# SensorNodePCB_set1_v2_wo_Relay.net
KiCad netlist of a schematic drawn in EAGLE
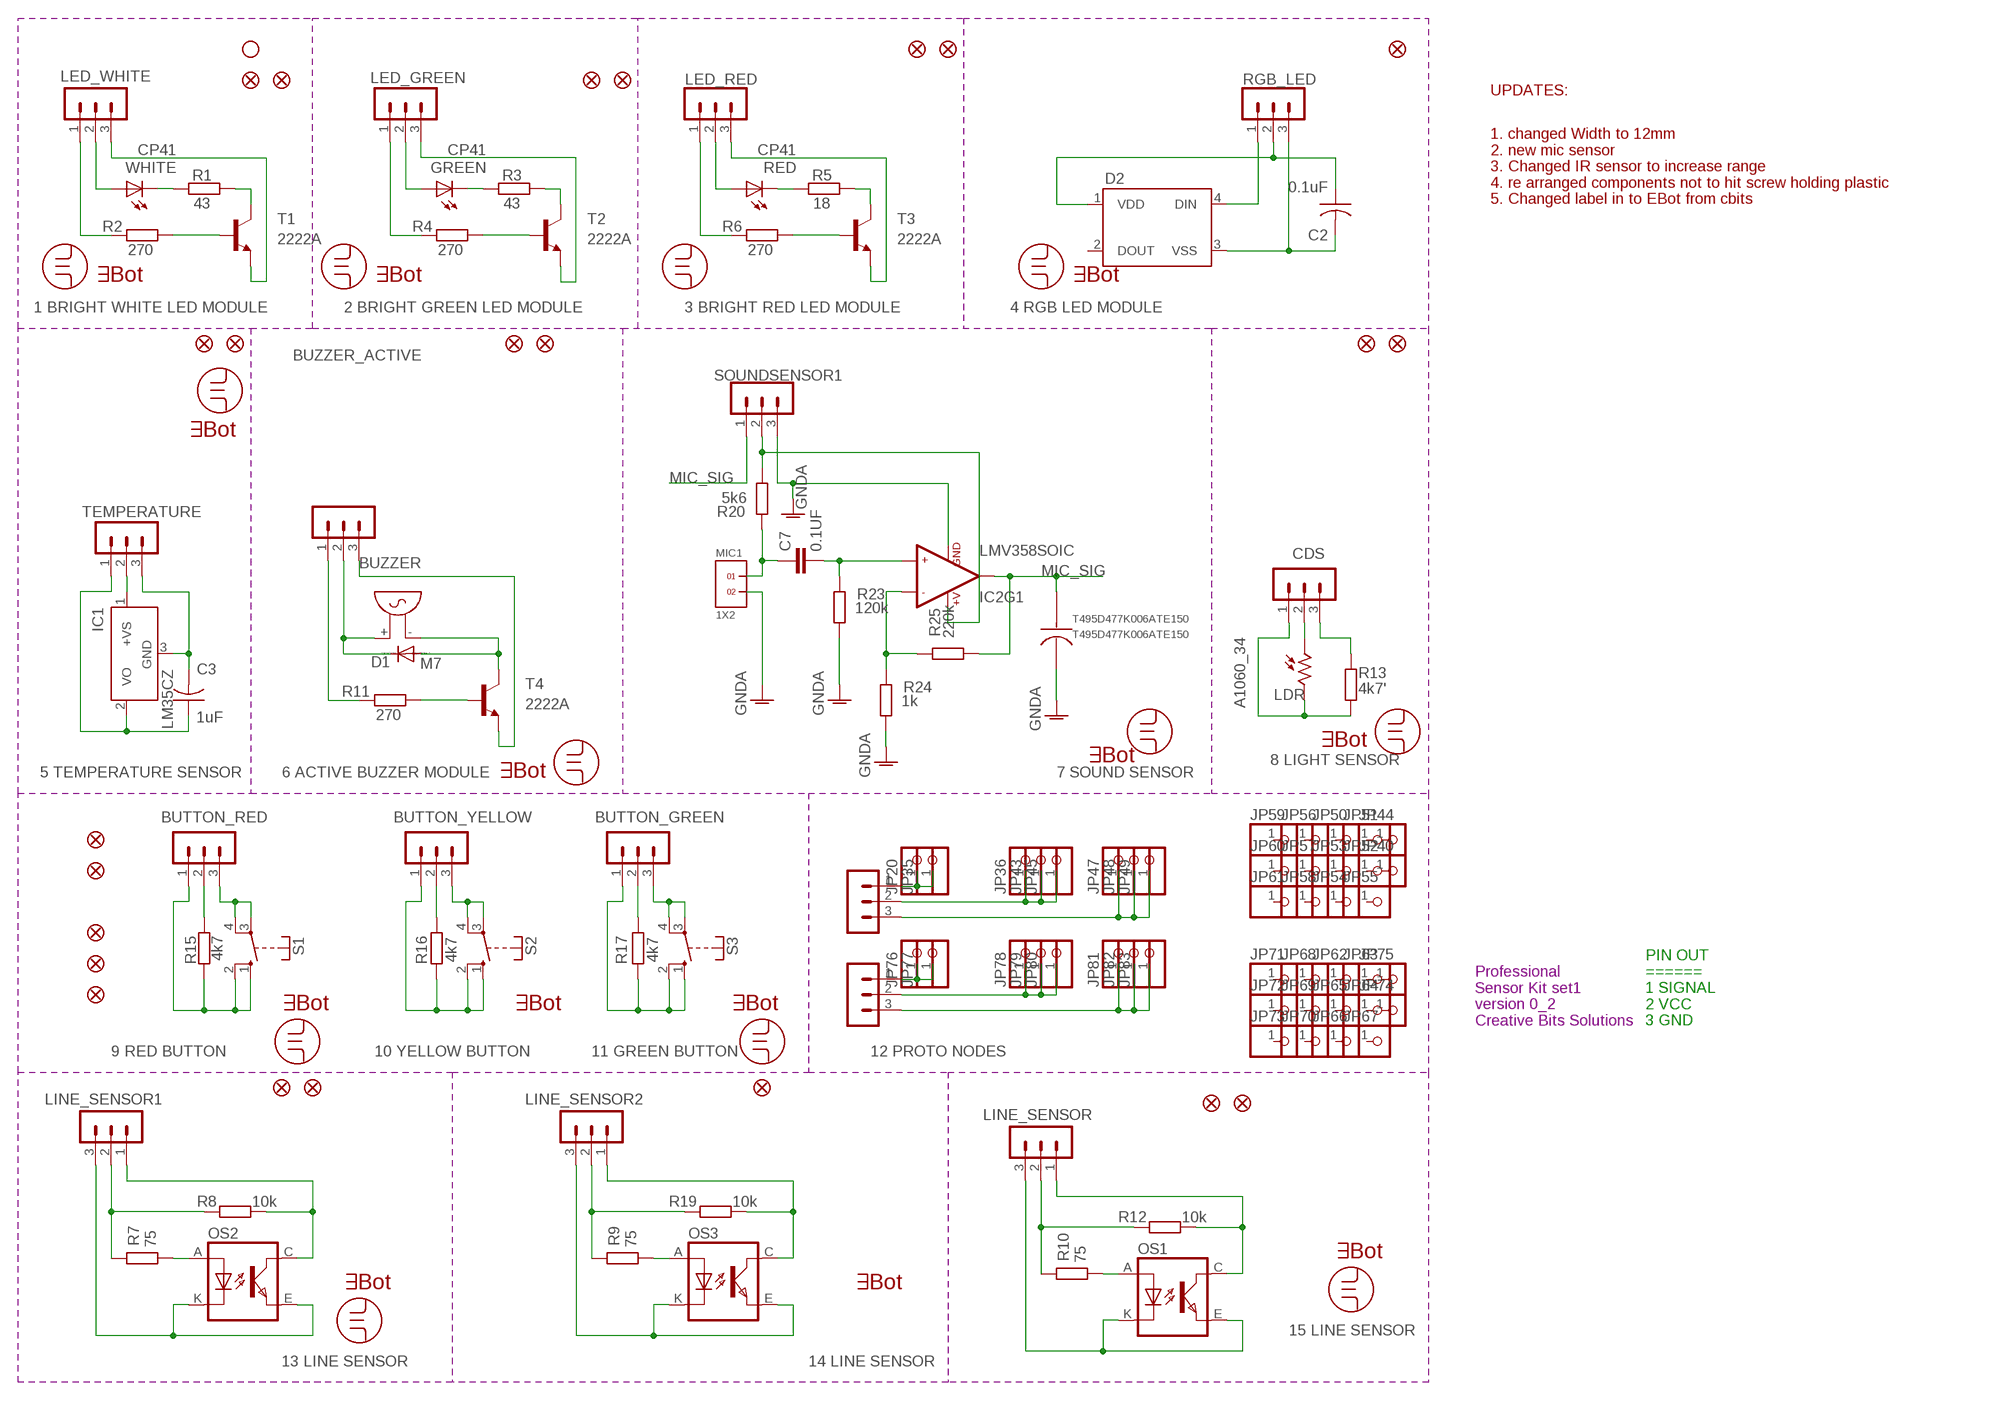
[diagram p0: schematic, sheet 1]

(export (version "E")
  (design (tool "Eeschema 10.0.6"))
  (components
    (comp (ref "BUTTON_GREEN")
      (value "MA03-1")
      (footprint "eagle-import:MA03-1")
      (libsource (lib "eagle-import") (part "MA03-1"))
    )
    (comp (ref "BUTTON_RED")
      (value "MA03-1")
      (footprint "eagle-import:MA03-1")
      (libsource (lib "eagle-import") (part "MA03-1"))
    )
    (comp (ref "BUTTON_YELLOW")
      (value "MA03-1")
      (footprint "eagle-import:MA03-1")
      (libsource (lib "eagle-import") (part "MA03-1"))
    )
    (comp (ref "BUZZER")
      (value "F/QMX")
      (footprint "eagle-import:F_QMX")
      (libsource (lib "eagle-import") (part "F/QMX"))
    )
    (comp (ref "BUZZER_ACTIVE")
      (value "MA03-1")
      (footprint "eagle-import:MA03-1")
      (libsource (lib "eagle-import") (part "MA03-1"))
    )
    (comp (ref "C2")
      (value "0.1uF")
      (footprint "eagle-import:C0805")
      (libsource (lib "eagle-import") (part "C-USC0805"))
    )
    (comp (ref "C3")
      (value "1uF")
      (footprint "eagle-import:C0805")
      (libsource (lib "eagle-import") (part "C-USC0805"))
    )
    (comp (ref "C7")
      (value "0.1UF")
      (footprint "eagle-import:0805")
      (libsource (lib "eagle-import") (part "CAP0805"))
    )
    (comp (ref "CDS")
      (value "MA03-1")
      (footprint "eagle-import:MA03-1")
      (libsource (lib "eagle-import") (part "MA03-1"))
    )
    (comp (ref "D1")
      (value "M7")
      (footprint "eagle-import:DO214AC")
      (libsource (lib "eagle-import") (part "DIODE-DO214AC"))
    )
    (comp (ref "D2")
      (value "WS2812B")
      (footprint "eagle-import:WS2812B")
      (libsource (lib "eagle-import") (part "WS2812B"))
    )
    (comp (ref "GREEN")
      (value "CP41")
      (footprint "eagle-import:CP41B")
      (libsource (lib "eagle-import") (part "LED-2AC-CP41B-WES"))
    )
    (comp (ref "IC1")
      (value "LM35CZ")
      (footprint "eagle-import:TO92")
      (libsource (lib "eagle-import") (part "LM35CZ"))
    )
    (comp (ref "IC2")
      (value "LMV358SOIC")
      (footprint "eagle-import:SO08")
      (libsource (lib "eagle-import") (part "LMV358SOIC"))
    )
    (comp (ref "JP1")
      (value "STAND-OFF")
      (footprint "eagle-import:STAND-OFF")
      (libsource (lib "eagle-import") (part "STAND-OFF"))
    )
    (comp (ref "JP2")
      (value "FIDUCIAL1X2")
      (footprint "eagle-import:FIDUCIAL-1X2")
      (libsource (lib "eagle-import") (part "FIDUCIAL1X2"))
    )
    (comp (ref "JP4")
      (value "FIDUCIAL1X2")
      (footprint "eagle-import:FIDUCIAL-1X2")
      (libsource (lib "eagle-import") (part "FIDUCIAL1X2"))
    )
    (comp (ref "JP6")
      (value "FIDUCIAL1X2")
      (footprint "eagle-import:FIDUCIAL-1X2")
      (libsource (lib "eagle-import") (part "FIDUCIAL1X2"))
    )
    (comp (ref "JP7")
      (value "FIDUCIAL1X2")
      (footprint "eagle-import:FIDUCIAL-1X2")
      (libsource (lib "eagle-import") (part "FIDUCIAL1X2"))
    )
    (comp (ref "JP12")
      (value "FIDUCIAL1X2")
      (footprint "eagle-import:FIDUCIAL-1X2")
      (libsource (lib "eagle-import") (part "FIDUCIAL1X2"))
    )
    (comp (ref "JP18")
      (value "FIDUCIAL1X2")
      (footprint "eagle-import:FIDUCIAL-1X2")
      (libsource (lib "eagle-import") (part "FIDUCIAL1X2"))
    )
    (comp (ref "JP19")
      (value "FIDUCIAL1X2")
      (footprint "eagle-import:FIDUCIAL-1X2")
      (libsource (lib "eagle-import") (part "FIDUCIAL1X2"))
    )
    (comp (ref "JP20")
      (value "PINHD-1X1CB")
      (footprint "eagle-import:1X01-CLEANBIG")
      (libsource (lib "eagle-import") (part "PINHD-1X1CB"))
    )
    (comp (ref "JP23")
      (value "FIDUCIAL1X2")
      (footprint "eagle-import:FIDUCIAL-1X2")
      (libsource (lib "eagle-import") (part "FIDUCIAL1X2"))
    )
    (comp (ref "JP24")
      (value "FIDUCIAL1X2")
      (footprint "eagle-import:FIDUCIAL-1X2")
      (libsource (lib "eagle-import") (part "FIDUCIAL1X2"))
    )
    (comp (ref "JP25")
      (value "FIDUCIAL1X2")
      (footprint "eagle-import:FIDUCIAL-1X2")
      (libsource (lib "eagle-import") (part "FIDUCIAL1X2"))
    )
    (comp (ref "JP26")
      (value "FIDUCIAL1X2")
      (footprint "eagle-import:FIDUCIAL-1X2")
      (libsource (lib "eagle-import") (part "FIDUCIAL1X2"))
    )
    (comp (ref "JP28")
      (value "FIDUCIAL1X2")
      (footprint "eagle-import:FIDUCIAL-1X2")
      (libsource (lib "eagle-import") (part "FIDUCIAL1X2"))
    )
    (comp (ref "JP29")
      (value "FIDUCIAL1X2")
      (footprint "eagle-import:FIDUCIAL-1X2")
      (libsource (lib "eagle-import") (part "FIDUCIAL1X2"))
    )
    (comp (ref "JP31")
      (value "FIDUCIAL1X2")
      (footprint "eagle-import:FIDUCIAL-1X2")
      (libsource (lib "eagle-import") (part "FIDUCIAL1X2"))
    )
    (comp (ref "JP32")
      (value "FIDUCIAL1X2")
      (footprint "eagle-import:FIDUCIAL-1X2")
      (libsource (lib "eagle-import") (part "FIDUCIAL1X2"))
    )
    (comp (ref "JP33")
      (value "FIDUCIAL1X2")
      (footprint "eagle-import:FIDUCIAL-1X2")
      (libsource (lib "eagle-import") (part "FIDUCIAL1X2"))
    )
    (comp (ref "JP34")
      (value "FIDUCIAL1X2")
      (footprint "eagle-import:FIDUCIAL-1X2")
      (libsource (lib "eagle-import") (part "FIDUCIAL1X2"))
    )
    (comp (ref "JP35")
      (value "PINHD-1X1CB")
      (footprint "eagle-import:1X01-CLEANBIG")
      (libsource (lib "eagle-import") (part "PINHD-1X1CB"))
    )
    (comp (ref "JP36")
      (value "PINHD-1X1CB")
      (footprint "eagle-import:1X01-CLEANBIG")
      (libsource (lib "eagle-import") (part "PINHD-1X1CB"))
    )
    (comp (ref "JP37")
      (value "FIDUCIAL1X2")
      (footprint "eagle-import:FIDUCIAL-1X2")
      (libsource (lib "eagle-import") (part "FIDUCIAL1X2"))
    )
    (comp (ref "JP38")
      (value "FIDUCIAL1X2")
      (footprint "eagle-import:FIDUCIAL-1X2")
      (libsource (lib "eagle-import") (part "FIDUCIAL1X2"))
    )
    (comp (ref "JP39")
      (value "FIDUCIAL1X2")
      (footprint "eagle-import:FIDUCIAL-1X2")
      (libsource (lib "eagle-import") (part "FIDUCIAL1X2"))
    )
    (comp (ref "JP40")
      (value "PINHD-1X1CB")
      (footprint "eagle-import:1X01-CLEANBIG")
      (libsource (lib "eagle-import") (part "PINHD-1X1CB"))
    )
    (comp (ref "JP41")
      (value "FIDUCIAL1X2")
      (footprint "eagle-import:FIDUCIAL-1X2")
      (libsource (lib "eagle-import") (part "FIDUCIAL1X2"))
    )
    (comp (ref "JP42")
      (value "FIDUCIAL1X2")
      (footprint "eagle-import:FIDUCIAL-1X2")
      (libsource (lib "eagle-import") (part "FIDUCIAL1X2"))
    )
    (comp (ref "JP43")
      (value "PINHD-1X1CB")
      (footprint "eagle-import:1X01-CLEANBIG")
      (libsource (lib "eagle-import") (part "PINHD-1X1CB"))
    )
    (comp (ref "JP44")
      (value "PINHD-1X1CB")
      (footprint "eagle-import:1X01-CLEANBIG")
      (libsource (lib "eagle-import") (part "PINHD-1X1CB"))
    )
    (comp (ref "JP45")
      (value "PINHD-1X1CB")
      (footprint "eagle-import:1X01-CLEANBIG")
      (libsource (lib "eagle-import") (part "PINHD-1X1CB"))
    )
    (comp (ref "JP46")
      (value "FIDUCIAL1X2")
      (footprint "eagle-import:FIDUCIAL-1X2")
      (libsource (lib "eagle-import") (part "FIDUCIAL1X2"))
    )
    (comp (ref "JP47")
      (value "PINHD-1X1CB")
      (footprint "eagle-import:1X01-CLEANBIG")
      (libsource (lib "eagle-import") (part "PINHD-1X1CB"))
    )
    (comp (ref "JP48")
      (value "PINHD-1X1CB")
      (footprint "eagle-import:1X01-CLEANBIG")
      (libsource (lib "eagle-import") (part "PINHD-1X1CB"))
    )
    (comp (ref "JP49")
      (value "PINHD-1X1CB")
      (footprint "eagle-import:1X01-CLEANBIG")
      (libsource (lib "eagle-import") (part "PINHD-1X1CB"))
    )
    (comp (ref "JP50")
      (value "PINHD-1X1CB")
      (footprint "eagle-import:1X01-CLEANBIG")
      (libsource (lib "eagle-import") (part "PINHD-1X1CB"))
    )
    (comp (ref "JP51")
      (value "PINHD-1X1CB")
      (footprint "eagle-import:1X01-CLEANBIG")
      (libsource (lib "eagle-import") (part "PINHD-1X1CB"))
    )
    (comp (ref "JP52")
      (value "PINHD-1X1CB")
      (footprint "eagle-import:1X01-CLEANBIG")
      (libsource (lib "eagle-import") (part "PINHD-1X1CB"))
    )
    (comp (ref "JP53")
      (value "PINHD-1X1CB")
      (footprint "eagle-import:1X01-CLEANBIG")
      (libsource (lib "eagle-import") (part "PINHD-1X1CB"))
    )
    (comp (ref "JP54")
      (value "PINHD-1X1CB")
      (footprint "eagle-import:1X01-CLEANBIG")
      (libsource (lib "eagle-import") (part "PINHD-1X1CB"))
    )
    (comp (ref "JP55")
      (value "PINHD-1X1CB")
      (footprint "eagle-import:1X01-CLEANBIG")
      (libsource (lib "eagle-import") (part "PINHD-1X1CB"))
    )
    (comp (ref "JP56")
      (value "PINHD-1X1CB")
      (footprint "eagle-import:1X01-CLEANBIG")
      (libsource (lib "eagle-import") (part "PINHD-1X1CB"))
    )
    (comp (ref "JP57")
      (value "PINHD-1X1CB")
      (footprint "eagle-import:1X01-CLEANBIG")
      (libsource (lib "eagle-import") (part "PINHD-1X1CB"))
    )
    (comp (ref "JP58")
      (value "PINHD-1X1CB")
      (footprint "eagle-import:1X01-CLEANBIG")
      (libsource (lib "eagle-import") (part "PINHD-1X1CB"))
    )
    (comp (ref "JP59")
      (value "PINHD-1X1CB")
      (footprint "eagle-import:1X01-CLEANBIG")
      (libsource (lib "eagle-import") (part "PINHD-1X1CB"))
    )
    (comp (ref "JP60")
      (value "PINHD-1X1CB")
      (footprint "eagle-import:1X01-CLEANBIG")
      (libsource (lib "eagle-import") (part "PINHD-1X1CB"))
    )
    (comp (ref "JP61")
      (value "PINHD-1X1CB")
      (footprint "eagle-import:1X01-CLEANBIG")
      (libsource (lib "eagle-import") (part "PINHD-1X1CB"))
    )
    (comp (ref "JP62")
      (value "PINHD-1X1CB")
      (footprint "eagle-import:1X01-CLEANBIG")
      (libsource (lib "eagle-import") (part "PINHD-1X1CB"))
    )
    (comp (ref "JP63")
      (value "PINHD-1X1CB")
      (footprint "eagle-import:1X01-CLEANBIG")
      (libsource (lib "eagle-import") (part "PINHD-1X1CB"))
    )
    (comp (ref "JP64")
      (value "PINHD-1X1CB")
      (footprint "eagle-import:1X01-CLEANBIG")
      (libsource (lib "eagle-import") (part "PINHD-1X1CB"))
    )
    (comp (ref "JP65")
      (value "PINHD-1X1CB")
      (footprint "eagle-import:1X01-CLEANBIG")
      (libsource (lib "eagle-import") (part "PINHD-1X1CB"))
    )
    (comp (ref "JP66")
      (value "PINHD-1X1CB")
      (footprint "eagle-import:1X01-CLEANBIG")
      (libsource (lib "eagle-import") (part "PINHD-1X1CB"))
    )
    (comp (ref "JP67")
      (value "PINHD-1X1CB")
      (footprint "eagle-import:1X01-CLEANBIG")
      (libsource (lib "eagle-import") (part "PINHD-1X1CB"))
    )
    (comp (ref "JP68")
      (value "PINHD-1X1CB")
      (footprint "eagle-import:1X01-CLEANBIG")
      (libsource (lib "eagle-import") (part "PINHD-1X1CB"))
    )
    (comp (ref "JP69")
      (value "PINHD-1X1CB")
      (footprint "eagle-import:1X01-CLEANBIG")
      (libsource (lib "eagle-import") (part "PINHD-1X1CB"))
    )
    (comp (ref "JP70")
      (value "PINHD-1X1CB")
      (footprint "eagle-import:1X01-CLEANBIG")
      (libsource (lib "eagle-import") (part "PINHD-1X1CB"))
    )
    (comp (ref "JP71")
      (value "PINHD-1X1CB")
      (footprint "eagle-import:1X01-CLEANBIG")
      (libsource (lib "eagle-import") (part "PINHD-1X1CB"))
    )
    (comp (ref "JP72")
      (value "PINHD-1X1CB")
      (footprint "eagle-import:1X01-CLEANBIG")
      (libsource (lib "eagle-import") (part "PINHD-1X1CB"))
    )
    (comp (ref "JP73")
      (value "PINHD-1X1CB")
      (footprint "eagle-import:1X01-CLEANBIG")
      (libsource (lib "eagle-import") (part "PINHD-1X1CB"))
    )
    (comp (ref "JP74")
      (value "PINHD-1X1CB")
      (footprint "eagle-import:1X01-CLEANBIG")
      (libsource (lib "eagle-import") (part "PINHD-1X1CB"))
    )
    (comp (ref "JP75")
      (value "PINHD-1X1CB")
      (footprint "eagle-import:1X01-CLEANBIG")
      (libsource (lib "eagle-import") (part "PINHD-1X1CB"))
    )
    (comp (ref "JP76")
      (value "PINHD-1X1CB")
      (footprint "eagle-import:1X01-CLEANBIG")
      (libsource (lib "eagle-import") (part "PINHD-1X1CB"))
    )
    (comp (ref "JP77")
      (value "PINHD-1X1CB")
      (footprint "eagle-import:1X01-CLEANBIG")
      (libsource (lib "eagle-import") (part "PINHD-1X1CB"))
    )
    (comp (ref "JP78")
      (value "PINHD-1X1CB")
      (footprint "eagle-import:1X01-CLEANBIG")
      (libsource (lib "eagle-import") (part "PINHD-1X1CB"))
    )
    (comp (ref "JP79")
      (value "PINHD-1X1CB")
      (footprint "eagle-import:1X01-CLEANBIG")
      (libsource (lib "eagle-import") (part "PINHD-1X1CB"))
    )
    (comp (ref "JP80")
      (value "PINHD-1X1CB")
      (footprint "eagle-import:1X01-CLEANBIG")
      (libsource (lib "eagle-import") (part "PINHD-1X1CB"))
    )
    (comp (ref "JP81")
      (value "PINHD-1X1CB")
      (footprint "eagle-import:1X01-CLEANBIG")
      (libsource (lib "eagle-import") (part "PINHD-1X1CB"))
    )
    (comp (ref "JP82")
      (value "PINHD-1X1CB")
      (footprint "eagle-import:1X01-CLEANBIG")
      (libsource (lib "eagle-import") (part "PINHD-1X1CB"))
    )
    (comp (ref "JP83")
      (value "PINHD-1X1CB")
      (footprint "eagle-import:1X01-CLEANBIG")
      (libsource (lib "eagle-import") (part "PINHD-1X1CB"))
    )
    (comp (ref "LDR")
      (value "A1060_34")
      (footprint "eagle-import:T0-46-A10XX")
      (libsource (lib "eagle-import") (part "A1060_34"))
    )
    (comp (ref "LED_GREEN")
      (value "MA03-1")
      (footprint "eagle-import:MA03-1")
      (libsource (lib "eagle-import") (part "MA03-1"))
    )
    (comp (ref "LED_RED")
      (value "MA03-1")
      (footprint "eagle-import:MA03-1")
      (libsource (lib "eagle-import") (part "MA03-1"))
    )
    (comp (ref "LED_WHITE")
      (value "MA03-1")
      (footprint "eagle-import:MA03-1")
      (libsource (lib "eagle-import") (part "MA03-1"))
    )
    (comp (ref "LINE_SENSOR")
      (value "MA03-1")
      (footprint "eagle-import:MA03-1")
      (libsource (lib "eagle-import") (part "MA03-1"))
    )
    (comp (ref "LINE_SENSOR1")
      (value "MA03-1")
      (footprint "eagle-import:MA03-1")
      (libsource (lib "eagle-import") (part "MA03-1"))
    )
    (comp (ref "LINE_SENSOR2")
      (value "MA03-1")
      (footprint "eagle-import:MA03-1")
      (libsource (lib "eagle-import") (part "MA03-1"))
    )
    (comp (ref "MIC1")
      (value "1X2")
      (footprint "eagle-import:1X2")
      (libsource (lib "eagle-import") (part "1X2"))
    )
    (comp (ref "OS1")
      (value "TCRT5000")
      (footprint "eagle-import:TCRT5000")
      (libsource (lib "eagle-import") (part "TCRT5000"))
    )
    (comp (ref "OS2")
      (value "TCRT5000")
      (footprint "eagle-import:TCRT5000")
      (libsource (lib "eagle-import") (part "TCRT5000"))
    )
    (comp (ref "OS3")
      (value "TCRT5000")
      (footprint "eagle-import:TCRT5000")
      (libsource (lib "eagle-import") (part "TCRT5000"))
    )
    (comp (ref "R1")
      (value "43")
      (footprint "eagle-import:R0805")
      (libsource (lib "eagle-import") (part "R-EU_R0805"))
    )
    (comp (ref "R2")
      (value "270")
      (footprint "eagle-import:R0805")
      (libsource (lib "eagle-import") (part "R-EU_R0805"))
    )
    (comp (ref "R3")
      (value "43")
      (footprint "eagle-import:R0805")
      (libsource (lib "eagle-import") (part "R-EU_R0805"))
    )
    (comp (ref "R4")
      (value "270")
      (footprint "eagle-import:R0805")
      (libsource (lib "eagle-import") (part "R-EU_R0805"))
    )
    (comp (ref "R5")
      (value "18")
      (footprint "eagle-import:R0805")
      (libsource (lib "eagle-import") (part "R-EU_R0805"))
    )
    (comp (ref "R6")
      (value "270")
      (footprint "eagle-import:R0805")
      (libsource (lib "eagle-import") (part "R-EU_R0805"))
    )
    (comp (ref "R7")
      (value "75")
      (footprint "eagle-import:R0805")
      (libsource (lib "eagle-import") (part "R-EU_R0805"))
    )
    (comp (ref "R8")
      (value "10k")
      (footprint "eagle-import:R0805")
      (libsource (lib "eagle-import") (part "R-EU_R0805"))
    )
    (comp (ref "R9")
      (value "75")
      (footprint "eagle-import:R0805")
      (libsource (lib "eagle-import") (part "R-EU_R0805"))
    )
    (comp (ref "R10")
      (value "75")
      (footprint "eagle-import:R0805")
      (libsource (lib "eagle-import") (part "R-EU_R0805"))
    )
    (comp (ref "R11")
      (value "270")
      (footprint "eagle-import:R0805")
      (libsource (lib "eagle-import") (part "R-EU_R0805"))
    )
    (comp (ref "R12")
      (value "10k")
      (footprint "eagle-import:R0805")
      (libsource (lib "eagle-import") (part "R-EU_R0805"))
    )
    (comp (ref "R13")
      (value "4k7'")
      (footprint "eagle-import:R0805")
      (libsource (lib "eagle-import") (part "R-EU_R0805"))
    )
    (comp (ref "R15")
      (value "4k7")
      (footprint "eagle-import:R0805")
      (libsource (lib "eagle-import") (part "R-EU_R0805"))
    )
    (comp (ref "R16")
      (value "4k7")
      (footprint "eagle-import:R0805")
      (libsource (lib "eagle-import") (part "R-EU_R0805"))
    )
    (comp (ref "R17")
      (value "4k7")
      (footprint "eagle-import:R0805")
      (libsource (lib "eagle-import") (part "R-EU_R0805"))
    )
    (comp (ref "R19")
      (value "10k")
      (footprint "eagle-import:R0805")
      (libsource (lib "eagle-import") (part "R-EU_R0805"))
    )
    (comp (ref "R20")
      (value "5k6")
      (footprint "eagle-import:R0805")
      (libsource (lib "eagle-import") (part "R-EU_R0805"))
    )
    (comp (ref "R23")
      (value "120k")
      (footprint "eagle-import:R0805")
      (libsource (lib "eagle-import") (part "R-EU_R0805"))
    )
    (comp (ref "R24")
      (value "1k")
      (footprint "eagle-import:R0805")
      (libsource (lib "eagle-import") (part "R-EU_R0805"))
    )
    (comp (ref "R25")
      (value "220k")
      (footprint "eagle-import:R0805")
      (libsource (lib "eagle-import") (part "R-EU_R0805"))
    )
    (comp (ref "RED")
      (value "CP41")
      (footprint "eagle-import:CP41B")
      (libsource (lib "eagle-import") (part "LED-2AC-CP41B-WES"))
    )
    (comp (ref "RGB_LED")
      (value "MA03-1")
      (footprint "eagle-import:MA03-1")
      (libsource (lib "eagle-import") (part "MA03-1"))
    )
    (comp (ref "S1")
      (value "RACON12")
      (footprint "eagle-import:RACON12")
      (libsource (lib "eagle-import") (part "RACON12"))
    )
    (comp (ref "S2")
      (value "RACON12")
      (footprint "eagle-import:RACON12")
      (libsource (lib "eagle-import") (part "RACON12"))
    )
    (comp (ref "S3")
      (value "RACON12")
      (footprint "eagle-import:RACON12")
      (libsource (lib "eagle-import") (part "RACON12"))
    )
    (comp (ref "SOUNDSENSOR1")
      (value "MA03-1")
      (footprint "eagle-import:MA03-1")
      (libsource (lib "eagle-import") (part "MA03-1"))
    )
    (comp (ref "T1")
      (value "2222A")
      (footprint "eagle-import:SOT23-3")
      (libsource (lib "eagle-import") (part "TRANSISTOR_NPNMMBT2222A"))
    )
    (comp (ref "T2")
      (value "2222A")
      (footprint "eagle-import:SOT23-3")
      (libsource (lib "eagle-import") (part "TRANSISTOR_NPNMMBT2222A"))
    )
    (comp (ref "T3")
      (value "2222A")
      (footprint "eagle-import:SOT23-3")
      (libsource (lib "eagle-import") (part "TRANSISTOR_NPNMMBT2222A"))
    )
    (comp (ref "T4")
      (value "2222A")
      (footprint "eagle-import:SOT23-3")
      (libsource (lib "eagle-import") (part "TRANSISTOR_NPNMMBT2222A"))
    )
    (comp (ref "TEMPERATURE")
      (value "MA03-1")
      (footprint "eagle-import:MA03-1")
      (libsource (lib "eagle-import") (part "MA03-1"))
    )
    (comp (ref "U$1")
      (value "EBOT_LOGO_6MMX6MM")
      (footprint "eagle-import:EBOT_6MMX6MM")
      (libsource (lib "eagle-import") (part "EBOT_LOGO_6MMX6MM"))
    )
    (comp (ref "U$3")
      (value "EBOT_LOGO_6MMX6MM")
      (footprint "eagle-import:EBOT_6MMX6MM")
      (libsource (lib "eagle-import") (part "EBOT_LOGO_6MMX6MM"))
    )
    (comp (ref "U$4")
      (value "EBOT_LOGO_6MMX6MM")
      (footprint "eagle-import:EBOT_6MMX6MM")
      (libsource (lib "eagle-import") (part "EBOT_LOGO_6MMX6MM"))
    )
    (comp (ref "U$6")
      (value "EBOT_LOGO_6MMX6MM")
      (footprint "eagle-import:EBOT_6MMX6MM")
      (libsource (lib "eagle-import") (part "EBOT_LOGO_6MMX6MM"))
    )
    (comp (ref "U$8")
      (value "EBOT_LOGO_6MMX6MM")
      (footprint "eagle-import:EBOT_6MMX6MM")
      (libsource (lib "eagle-import") (part "EBOT_LOGO_6MMX6MM"))
    )
    (comp (ref "U$9")
      (value "EBOT_LOGO_6MMX6MM")
      (footprint "eagle-import:EBOT_6MMX6MM")
      (libsource (lib "eagle-import") (part "EBOT_LOGO_6MMX6MM"))
    )
    (comp (ref "U$10")
      (value "EBOT_LOGO_6MMX6MM")
      (footprint "eagle-import:EBOT_6MMX6MM")
      (libsource (lib "eagle-import") (part "EBOT_LOGO_6MMX6MM"))
    )
    (comp (ref "U$11")
      (value "T495D477K006ATE150")
      (footprint "eagle-import:T495D477K006ATE150")
      (libsource (lib "eagle-import") (part "T495D477K006ATE150"))
    )
    (comp (ref "U$12")
      (value "EBOT_LOGO_6MMX6MM")
      (footprint "eagle-import:EBOT_6MMX6MM")
      (libsource (lib "eagle-import") (part "EBOT_LOGO_6MMX6MM"))
    )
    (comp (ref "U$13")
      (value "EBOT_LOGO_6MMX6MM")
      (footprint "eagle-import:EBOT_6MMX6MM")
      (libsource (lib "eagle-import") (part "EBOT_LOGO_6MMX6MM"))
    )
    (comp (ref "U$14")
      (value "EBOT_LOGO_6MMX6MM")
      (footprint "eagle-import:EBOT_6MMX6MM")
      (libsource (lib "eagle-import") (part "EBOT_LOGO_6MMX6MM"))
    )
    (comp (ref "U$15")
      (value "EBOT_LOGO_6MMX6MM")
      (footprint "eagle-import:EBOT_6MMX6MM")
      (libsource (lib "eagle-import") (part "EBOT_LOGO_6MMX6MM"))
    )
    (comp (ref "U$16")
      (value "EBOT_LOGO_6MMX6MM")
      (footprint "eagle-import:EBOT_6MMX6MM")
      (libsource (lib "eagle-import") (part "EBOT_LOGO_6MMX6MM"))
    )
    (comp (ref "U$17")
      (value "EBOT_NAME_6MM")
      (footprint "eagle-import:EBOT_NAME_6MM")
      (libsource (lib "eagle-import") (part "EBOT_NAME_6MM"))
    )
    (comp (ref "U$18")
      (value "EBOT_NAME_6MM")
      (footprint "eagle-import:EBOT_NAME_6MM")
      (libsource (lib "eagle-import") (part "EBOT_NAME_6MM"))
    )
    (comp (ref "U$20")
      (value "EBOT_NAME_6MM")
      (footprint "eagle-import:EBOT_NAME_6MM")
      (libsource (lib "eagle-import") (part "EBOT_NAME_6MM"))
    )
    (comp (ref "U$21")
      (value "EBOT_NAME_6MM")
      (footprint "eagle-import:EBOT_NAME_6MM")
      (libsource (lib "eagle-import") (part "EBOT_NAME_6MM"))
    )
    (comp (ref "U$22")
      (value "EBOT_NAME_6MM")
      (footprint "eagle-import:EBOT_NAME_6MM")
      (libsource (lib "eagle-import") (part "EBOT_NAME_6MM"))
    )
    (comp (ref "U$23")
      (value "EBOT_NAME_6MM")
      (footprint "eagle-import:EBOT_NAME_6MM")
      (libsource (lib "eagle-import") (part "EBOT_NAME_6MM"))
    )
    (comp (ref "U$24")
      (value "EBOT_NAME_6MM")
      (footprint "eagle-import:EBOT_NAME_6MM")
      (libsource (lib "eagle-import") (part "EBOT_NAME_6MM"))
    )
    (comp (ref "U$25")
      (value "EBOT_NAME_6MM")
      (footprint "eagle-import:EBOT_NAME_6MM")
      (libsource (lib "eagle-import") (part "EBOT_NAME_6MM"))
    )
    (comp (ref "U$26")
      (value "EBOT_NAME_6MM")
      (footprint "eagle-import:EBOT_NAME_6MM")
      (libsource (lib "eagle-import") (part "EBOT_NAME_6MM"))
    )
    (comp (ref "U$27")
      (value "EBOT_NAME_6MM")
      (footprint "eagle-import:EBOT_NAME_6MM")
      (libsource (lib "eagle-import") (part "EBOT_NAME_6MM"))
    )
    (comp (ref "U$29")
      (value "EBOT_NAME_6MM")
      (footprint "eagle-import:EBOT_NAME_6MM")
      (libsource (lib "eagle-import") (part "EBOT_NAME_6MM"))
    )
    (comp (ref "U$30")
      (value "EBOT_NAME_6MM")
      (footprint "eagle-import:EBOT_NAME_6MM")
      (libsource (lib "eagle-import") (part "EBOT_NAME_6MM"))
    )
    (comp (ref "U$31")
      (value "EBOT_NAME_6MM")
      (footprint "eagle-import:EBOT_NAME_6MM")
      (libsource (lib "eagle-import") (part "EBOT_NAME_6MM"))
    )
    (comp (ref "ULTRASONICSENSOR1")
      (value "MA03-1")
      (footprint "eagle-import:MA03-1")
      (libsource (lib "eagle-import") (part "MA03-1"))
    )
    (comp (ref "ULTRASONICSENSOR2")
      (value "MA03-1")
      (footprint "eagle-import:MA03-1")
      (libsource (lib "eagle-import") (part "MA03-1"))
    )
    (comp (ref "WHITE")
      (value "CP41")
      (footprint "eagle-import:CP41B")
      (libsource (lib "eagle-import") (part "LED-2AC-CP41B-WES"))
    )
  )
  (nets
    (net (code "1") (name "/MIC_SIG") (class "Default")
      (node (ref "IC2") (pin "1") (pinfunction "OUT1_1") (pintype "output"))
      (node (ref "R25") (pin "1") (pinfunction "1_1") (pintype "passive"))
      (node (ref "SOUNDSENSOR1") (pin "1") (pinfunction "1_1") (pintype "passive"))
      (node (ref "U$11") (pin "+") (pinfunction "+_+") (pintype "bidirectional"))
    )
    (net (code "2") (name "GNDA") (class "Default")
      (node (ref "IC2") (pin "4") (pinfunction "GND_4") (pintype "power_in"))
      (node (ref "MIC1") (pin "2") (pinfunction "2_2") (pintype "bidirectional"))
      (node (ref "R23") (pin "1") (pinfunction "1_1") (pintype "passive"))
      (node (ref "R24") (pin "1") (pinfunction "1_1") (pintype "passive"))
      (node (ref "SOUNDSENSOR1") (pin "3") (pinfunction "3_3") (pintype "passive"))
      (node (ref "U$11") (pin "-") (pinfunction "-_-") (pintype "bidirectional"))
    )
    (net (code "3") (name "Net-(BUTTON_GREEN-Pad1)") (class "Default")
      (node (ref "BUTTON_GREEN") (pin "1") (pinfunction "1_1") (pintype "passive"))
      (node (ref "R17") (pin "2") (pinfunction "2_2") (pintype "passive"))
      (node (ref "S3") (pin "1") (pinfunction "S_1") (pintype "passive"))
      (node (ref "S3") (pin "2") (pinfunction "S_2") (pintype "passive"))
    )
    (net (code "4") (name "Net-(BUTTON_GREEN-Pad2)") (class "Default")
      (node (ref "BUTTON_GREEN") (pin "2") (pinfunction "2_2") (pintype "passive"))
      (node (ref "R17") (pin "1") (pinfunction "1_1") (pintype "passive"))
    )
    (net (code "5") (name "Net-(BUTTON_GREEN-Pad3)") (class "Default")
      (node (ref "BUTTON_GREEN") (pin "3") (pinfunction "3_3") (pintype "passive"))
      (node (ref "S3") (pin "3") (pinfunction "P_3") (pintype "passive"))
      (node (ref "S3") (pin "4") (pinfunction "P_4") (pintype "passive"))
    )
    (net (code "6") (name "Net-(BUTTON_RED-Pad1)") (class "Default")
      (node (ref "BUTTON_RED") (pin "1") (pinfunction "1_1") (pintype "passive"))
      (node (ref "R15") (pin "2") (pinfunction "2_2") (pintype "passive"))
      (node (ref "S1") (pin "1") (pinfunction "S_1") (pintype "passive"))
      (node (ref "S1") (pin "2") (pinfunction "S_2") (pintype "passive"))
    )
    (net (code "7") (name "Net-(BUTTON_RED-Pad2)") (class "Default")
      (node (ref "BUTTON_RED") (pin "2") (pinfunction "2_2") (pintype "passive"))
      (node (ref "R15") (pin "1") (pinfunction "1_1") (pintype "passive"))
    )
    (net (code "8") (name "Net-(BUTTON_RED-Pad3)") (class "Default")
      (node (ref "BUTTON_RED") (pin "3") (pinfunction "3_3") (pintype "passive"))
      (node (ref "S1") (pin "3") (pinfunction "P_3") (pintype "passive"))
      (node (ref "S1") (pin "4") (pinfunction "P_4") (pintype "passive"))
    )
    (net (code "9") (name "Net-(BUTTON_YELLOW-Pad1)") (class "Default")
      (node (ref "BUTTON_YELLOW") (pin "1") (pinfunction "1_1") (pintype "passive"))
      (node (ref "R16") (pin "2") (pinfunction "2_2") (pintype "passive"))
      (node (ref "S2") (pin "1") (pinfunction "S_1") (pintype "passive"))
      (node (ref "S2") (pin "2") (pinfunction "S_2") (pintype "passive"))
    )
    (net (code "10") (name "Net-(BUTTON_YELLOW-Pad2)") (class "Default")
      (node (ref "BUTTON_YELLOW") (pin "2") (pinfunction "2_2") (pintype "passive"))
      (node (ref "R16") (pin "1") (pinfunction "1_1") (pintype "passive"))
    )
    (net (code "11") (name "Net-(BUTTON_YELLOW-Pad3)") (class "Default")
      (node (ref "BUTTON_YELLOW") (pin "3") (pinfunction "3_3") (pintype "passive"))
      (node (ref "S2") (pin "3") (pinfunction "P_3") (pintype "passive"))
      (node (ref "S2") (pin "4") (pinfunction "P_4") (pintype "passive"))
    )
    (net (code "12") (name "Net-(BUZZER-1)") (class "Default")
      (node (ref "BUZZER") (pin "-") (pinfunction "1_-") (pintype "passive"))
      (node (ref "D1") (pin "A") (pinfunction "A_A") (pintype "passive"))
      (node (ref "T4") (pin "3") (pinfunction "C_3") (pintype "passive"))
    )
    (net (code "13") (name "Net-(BUZZER-2)") (class "Default")
      (node (ref "BUZZER") (pin "+") (pinfunction "2_+") (pintype "passive"))
      (node (ref "BUZZER_ACTIVE") (pin "2") (pinfunction "2_2") (pintype "passive"))
      (node (ref "D1") (pin "C") (pinfunction "C_C") (pintype "passive"))
    )
    (net (code "14") (name "Net-(BUZZER_ACTIVE-Pad1)") (class "Default")
      (node (ref "BUZZER_ACTIVE") (pin "1") (pinfunction "1_1") (pintype "passive"))
      (node (ref "R11") (pin "2") (pinfunction "2_2") (pintype "passive"))
    )
    (net (code "15") (name "Net-(C7-Pad1)") (class "Default")
      (node (ref "C7") (pin "1") (pinfunction "1_1") (pintype "passive"))
      (node (ref "MIC1") (pin "1") (pinfunction "1_1") (pintype "bidirectional"))
      (node (ref "R20") (pin "2") (pinfunction "2_2") (pintype "passive"))
    )
    (net (code "16") (name "Net-(CDS-Pad1)") (class "Default")
      (node (ref "CDS") (pin "1") (pinfunction "1_1") (pintype "passive"))
      (node (ref "LDR") (pin "2") (pinfunction "2_2") (pintype "passive"))
      (node (ref "R13") (pin "2") (pinfunction "2_2") (pintype "passive"))
    )
    (net (code "17") (name "Net-(CDS-Pad2)") (class "Default")
      (node (ref "CDS") (pin "2") (pinfunction "2_2") (pintype "passive"))
      (node (ref "LDR") (pin "1") (pinfunction "1_1") (pintype "passive"))
    )
    (net (code "18") (name "Net-(CDS-Pad3)") (class "Default")
      (node (ref "CDS") (pin "3") (pinfunction "3_3") (pintype "passive"))
      (node (ref "R13") (pin "1") (pinfunction "1_1") (pintype "passive"))
    )
    (net (code "19") (name "Net-(D2-DIN)") (class "Default")
      (node (ref "D2") (pin "4") (pinfunction "DIN_4") (pintype "input"))
      (node (ref "RGB_LED") (pin "1") (pinfunction "1_1") (pintype "passive"))
    )
    (net (code "20") (name "Net-(D2-VDD)") (class "Default")
      (node (ref "C2") (pin "1") (pinfunction "1_1") (pintype "passive"))
      (node (ref "D2") (pin "1") (pinfunction "VDD_1") (pintype "power_in"))
      (node (ref "RGB_LED") (pin "2") (pinfunction "2_2") (pintype "passive"))
    )
    (net (code "21") (name "Net-(D2-VSS)") (class "Default")
      (node (ref "C2") (pin "2") (pinfunction "2_2") (pintype "passive"))
      (node (ref "D2") (pin "3") (pinfunction "VSS_3") (pintype "power_in"))
      (node (ref "RGB_LED") (pin "3") (pinfunction "3_3") (pintype "passive"))
    )
    (net (code "22") (name "Net-(GREEN-A-Pad2)") (class "Default")
      (node (ref "GREEN") (pin "2") (pinfunction "A_2") (pintype "passive"))
      (node (ref "GREEN") (pin "3") (pinfunction "A_3") (pintype "passive"))
      (node (ref "LED_GREEN") (pin "2") (pinfunction "2_2") (pintype "passive"))
    )
    (net (code "23") (name "Net-(GREEN-C-Pad1)") (class "Default")
      (node (ref "GREEN") (pin "1") (pinfunction "C_1") (pintype "passive"))
      (node (ref "GREEN") (pin "4") (pinfunction "C_4") (pintype "passive"))
      (node (ref "R3") (pin "2") (pinfunction "2_2") (pintype "passive"))
    )
    (net (code "24") (name "Net-(IC1-+VS)") (class "Default")
      (node (ref "IC1") (pin "1") (pinfunction "+VS_1") (pintype "input"))
      (node (ref "TEMPERATURE") (pin "2") (pinfunction "2_2") (pintype "passive"))
    )
    (net (code "25") (name "Net-(IC1-GND)") (class "Default")
      (node (ref "C3") (pin "2") (pinfunction "2_2") (pintype "passive"))
      (node (ref "IC1") (pin "3") (pinfunction "GND_3") (pintype "power_in"))
      (node (ref "TEMPERATURE") (pin "3") (pinfunction "3_3") (pintype "passive"))
    )
    (net (code "26") (name "Net-(IC1-VO)") (class "Default")
      (node (ref "C3") (pin "1") (pinfunction "1_1") (pintype "passive"))
      (node (ref "IC1") (pin "2") (pinfunction "VO_2") (pintype "input"))
      (node (ref "TEMPERATURE") (pin "1") (pinfunction "1_1") (pintype "passive"))
    )
    (net (code "27") (name "Net-(IC2A-+IN1)") (class "Default")
      (node (ref "C7") (pin "2") (pinfunction "2_2") (pintype "passive"))
      (node (ref "IC2") (pin "3") (pinfunction "+IN1_3") (pintype "input"))
      (node (ref "R23") (pin "2") (pinfunction "2_2") (pintype "passive"))
    )
    (net (code "28") (name "Net-(IC2A-+V)") (class "Default")
      (node (ref "IC2") (pin "8") (pinfunction "+V_8") (pintype "power_in"))
      (node (ref "R20") (pin "1") (pinfunction "1_1") (pintype "passive"))
      (node (ref "SOUNDSENSOR1") (pin "2") (pinfunction "2_2") (pintype "passive"))
    )
    (net (code "29") (name "Net-(IC2A--IN1)") (class "Default")
      (node (ref "IC2") (pin "2") (pinfunction "-IN1_2") (pintype "input"))
      (node (ref "R24") (pin "2") (pinfunction "2_2") (pintype "passive"))
      (node (ref "R25") (pin "2") (pinfunction "2_2") (pintype "passive"))
    )
    (net (code "30") (name "Net-(JP20-Pad1)") (class "Default")
      (node (ref "JP20") (pin "1") (pinfunction "1_1") (pintype "passive"))
      (node (ref "JP35") (pin "1") (pinfunction "1_1") (pintype "passive"))
      (node (ref "ULTRASONICSENSOR1") (pin "1") (pinfunction "1_1") (pintype "passive"))
    )
    (net (code "31") (name "Net-(JP36-Pad1)") (class "Default")
      (node (ref "JP36") (pin "1") (pinfunction "1_1") (pintype "passive"))
      (node (ref "JP43") (pin "1") (pinfunction "1_1") (pintype "passive"))
      (node (ref "JP45") (pin "1") (pinfunction "1_1") (pintype "passive"))
      (node (ref "ULTRASONICSENSOR1") (pin "2") (pinfunction "2_2") (pintype "passive"))
    )
    (net (code "32") (name "Net-(JP47-Pad1)") (class "Default")
      (node (ref "JP47") (pin "1") (pinfunction "1_1") (pintype "passive"))
      (node (ref "JP48") (pin "1") (pinfunction "1_1") (pintype "passive"))
      (node (ref "JP49") (pin "1") (pinfunction "1_1") (pintype "passive"))
      (node (ref "ULTRASONICSENSOR1") (pin "3") (pinfunction "3_3") (pintype "passive"))
    )
    (net (code "33") (name "Net-(JP76-Pad1)") (class "Default")
      (node (ref "JP76") (pin "1") (pinfunction "1_1") (pintype "passive"))
      (node (ref "JP77") (pin "1") (pinfunction "1_1") (pintype "passive"))
      (node (ref "ULTRASONICSENSOR2") (pin "1") (pinfunction "1_1") (pintype "passive"))
    )
    (net (code "34") (name "Net-(JP78-Pad1)") (class "Default")
      (node (ref "JP78") (pin "1") (pinfunction "1_1") (pintype "passive"))
      (node (ref "JP79") (pin "1") (pinfunction "1_1") (pintype "passive"))
      (node (ref "JP80") (pin "1") (pinfunction "1_1") (pintype "passive"))
      (node (ref "ULTRASONICSENSOR2") (pin "2") (pinfunction "2_2") (pintype "passive"))
    )
    (net (code "35") (name "Net-(JP81-Pad1)") (class "Default")
      (node (ref "JP81") (pin "1") (pinfunction "1_1") (pintype "passive"))
      (node (ref "JP82") (pin "1") (pinfunction "1_1") (pintype "passive"))
      (node (ref "JP83") (pin "1") (pinfunction "1_1") (pintype "passive"))
      (node (ref "ULTRASONICSENSOR2") (pin "3") (pinfunction "3_3") (pintype "passive"))
    )
    (net (code "36") (name "Net-(LED_GREEN-Pad1)") (class "Default")
      (node (ref "LED_GREEN") (pin "1") (pinfunction "1_1") (pintype "passive"))
      (node (ref "R4") (pin "2") (pinfunction "2_2") (pintype "passive"))
    )
    (net (code "37") (name "Net-(LED_RED-Pad1)") (class "Default")
      (node (ref "LED_RED") (pin "1") (pinfunction "1_1") (pintype "passive"))
      (node (ref "R6") (pin "2") (pinfunction "2_2") (pintype "passive"))
    )
    (net (code "38") (name "Net-(LED_RED-Pad2)") (class "Default")
      (node (ref "LED_RED") (pin "2") (pinfunction "2_2") (pintype "passive"))
      (node (ref "RED") (pin "2") (pinfunction "A_2") (pintype "passive"))
      (node (ref "RED") (pin "3") (pinfunction "A_3") (pintype "passive"))
    )
    (net (code "39") (name "Net-(LED_WHITE-Pad1)") (class "Default")
      (node (ref "LED_WHITE") (pin "1") (pinfunction "1_1") (pintype "passive"))
      (node (ref "R2") (pin "2") (pinfunction "2_2") (pintype "passive"))
    )
    (net (code "40") (name "Net-(LED_WHITE-Pad2)") (class "Default")
      (node (ref "LED_WHITE") (pin "2") (pinfunction "2_2") (pintype "passive"))
      (node (ref "WHITE") (pin "2") (pinfunction "A_2") (pintype "passive"))
      (node (ref "WHITE") (pin "3") (pinfunction "A_3") (pintype "passive"))
    )
    (net (code "41") (name "Net-(LINE_SENSOR-Pad2)") (class "Default")
      (node (ref "LINE_SENSOR") (pin "2") (pinfunction "2_2") (pintype "passive"))
      (node (ref "R10") (pin "1") (pinfunction "1_1") (pintype "passive"))
      (node (ref "R12") (pin "1") (pinfunction "1_1") (pintype "passive"))
    )
    (net (code "42") (name "Net-(LINE_SENSOR1-Pad2)") (class "Default")
      (node (ref "LINE_SENSOR1") (pin "2") (pinfunction "2_2") (pintype "passive"))
      (node (ref "R7") (pin "1") (pinfunction "1_1") (pintype "passive"))
      (node (ref "R8") (pin "1") (pinfunction "1_1") (pintype "passive"))
    )
    (net (code "43") (name "Net-(LINE_SENSOR2-Pad2)") (class "Default")
      (node (ref "LINE_SENSOR2") (pin "2") (pinfunction "2_2") (pintype "passive"))
      (node (ref "R19") (pin "1") (pinfunction "1_1") (pintype "passive"))
      (node (ref "R9") (pin "1") (pinfunction "1_1") (pintype "passive"))
    )
    (net (code "44") (name "Net-(OS1-ANODE)") (class "Default")
      (node (ref "OS1") (pin "A") (pinfunction "ANODE_A") (pintype "passive"))
      (node (ref "R10") (pin "2") (pinfunction "2_2") (pintype "passive"))
    )
    (net (code "45") (name "Net-(OS1-CATHODE)") (class "Default")
      (node (ref "LINE_SENSOR") (pin "3") (pinfunction "3_3") (pintype "passive"))
      (node (ref "OS1") (pin "E") (pinfunction "EMITTER_E") (pintype "passive"))
      (node (ref "OS1") (pin "K") (pinfunction "CATHODE_K") (pintype "passive"))
    )
    (net (code "46") (name "Net-(OS1-COLLECTOR)") (class "Default")
      (node (ref "LINE_SENSOR") (pin "1") (pinfunction "1_1") (pintype "passive"))
      (node (ref "OS1") (pin "C") (pinfunction "COLLECTOR_C") (pintype "passive"))
      (node (ref "R12") (pin "2") (pinfunction "2_2") (pintype "passive"))
    )
    (net (code "47") (name "Net-(OS2-ANODE)") (class "Default")
      (node (ref "OS2") (pin "A") (pinfunction "ANODE_A") (pintype "passive"))
      (node (ref "R7") (pin "2") (pinfunction "2_2") (pintype "passive"))
    )
    (net (code "48") (name "Net-(OS2-CATHODE)") (class "Default")
      (node (ref "LINE_SENSOR1") (pin "3") (pinfunction "3_3") (pintype "passive"))
      (node (ref "OS2") (pin "E") (pinfunction "EMITTER_E") (pintype "passive"))
      (node (ref "OS2") (pin "K") (pinfunction "CATHODE_K") (pintype "passive"))
    )
    (net (code "49") (name "Net-(OS2-COLLECTOR)") (class "Default")
      (node (ref "LINE_SENSOR1") (pin "1") (pinfunction "1_1") (pintype "passive"))
      (node (ref "OS2") (pin "C") (pinfunction "COLLECTOR_C") (pintype "passive"))
      (node (ref "R8") (pin "2") (pinfunction "2_2") (pintype "passive"))
    )
    (net (code "50") (name "Net-(OS3-ANODE)") (class "Default")
      (node (ref "OS3") (pin "A") (pinfunction "ANODE_A") (pintype "passive"))
      (node (ref "R9") (pin "2") (pinfunction "2_2") (pintype "passive"))
    )
    (net (code "51") (name "Net-(OS3-CATHODE)") (class "Default")
      (node (ref "LINE_SENSOR2") (pin "3") (pinfunction "3_3") (pintype "passive"))
      (node (ref "OS3") (pin "E") (pinfunction "EMITTER_E") (pintype "passive"))
      (node (ref "OS3") (pin "K") (pinfunction "CATHODE_K") (pintype "passive"))
    )
    (net (code "52") (name "Net-(OS3-COLLECTOR)") (class "Default")
      (node (ref "LINE_SENSOR2") (pin "1") (pinfunction "1_1") (pintype "passive"))
      (node (ref "OS3") (pin "C") (pinfunction "COLLECTOR_C") (pintype "passive"))
      (node (ref "R19") (pin "2") (pinfunction "2_2") (pintype "passive"))
    )
    (net (code "53") (name "Net-(R1-Pad2)") (class "Default")
      (node (ref "R1") (pin "2") (pinfunction "2_2") (pintype "passive"))
      (node (ref "WHITE") (pin "1") (pinfunction "C_1") (pintype "passive"))
      (node (ref "WHITE") (pin "4") (pinfunction "C_4") (pintype "passive"))
    )
    (net (code "54") (name "Net-(R5-Pad2)") (class "Default")
      (node (ref "R5") (pin "2") (pinfunction "2_2") (pintype "passive"))
      (node (ref "RED") (pin "1") (pinfunction "C_1") (pintype "passive"))
      (node (ref "RED") (pin "4") (pinfunction "C_4") (pintype "passive"))
    )
    (net (code "55") (name "Net-(T1-B)") (class "Default")
      (node (ref "R2") (pin "1") (pinfunction "1_1") (pintype "passive"))
      (node (ref "T1") (pin "1") (pinfunction "B_1") (pintype "passive"))
    )
    (net (code "56") (name "Net-(T1-C)") (class "Default")
      (node (ref "R1") (pin "1") (pinfunction "1_1") (pintype "passive"))
      (node (ref "T1") (pin "3") (pinfunction "C_3") (pintype "passive"))
    )
    (net (code "57") (name "Net-(T1-E)") (class "Default")
      (node (ref "LED_WHITE") (pin "3") (pinfunction "3_3") (pintype "passive"))
      (node (ref "T1") (pin "2") (pinfunction "E_2") (pintype "passive"))
    )
    (net (code "58") (name "Net-(T2-B)") (class "Default")
      (node (ref "R4") (pin "1") (pinfunction "1_1") (pintype "passive"))
      (node (ref "T2") (pin "1") (pinfunction "B_1") (pintype "passive"))
    )
    (net (code "59") (name "Net-(T2-C)") (class "Default")
      (node (ref "R3") (pin "1") (pinfunction "1_1") (pintype "passive"))
      (node (ref "T2") (pin "3") (pinfunction "C_3") (pintype "passive"))
    )
    (net (code "60") (name "Net-(T2-E)") (class "Default")
      (node (ref "LED_GREEN") (pin "3") (pinfunction "3_3") (pintype "passive"))
      (node (ref "T2") (pin "2") (pinfunction "E_2") (pintype "passive"))
    )
    (net (code "61") (name "Net-(T3-B)") (class "Default")
      (node (ref "R6") (pin "1") (pinfunction "1_1") (pintype "passive"))
      (node (ref "T3") (pin "1") (pinfunction "B_1") (pintype "passive"))
    )
    (net (code "62") (name "Net-(T3-C)") (class "Default")
      (node (ref "R5") (pin "1") (pinfunction "1_1") (pintype "passive"))
      (node (ref "T3") (pin "3") (pinfunction "C_3") (pintype "passive"))
    )
    (net (code "63") (name "Net-(T3-E)") (class "Default")
      (node (ref "LED_RED") (pin "3") (pinfunction "3_3") (pintype "passive"))
      (node (ref "T3") (pin "2") (pinfunction "E_2") (pintype "passive"))
    )
    (net (code "64") (name "Net-(T4-B)") (class "Default")
      (node (ref "R11") (pin "1") (pinfunction "1_1") (pintype "passive"))
      (node (ref "T4") (pin "1") (pinfunction "B_1") (pintype "passive"))
    )
    (net (code "65") (name "Net-(T4-E)") (class "Default")
      (node (ref "BUZZER_ACTIVE") (pin "3") (pinfunction "3_3") (pintype "passive"))
      (node (ref "T4") (pin "2") (pinfunction "E_2") (pintype "passive"))
    )
    (net (code "66") (name "unconnected-(D2-DOUT-Pad2)") (class "Default")
      (node (ref "D2") (pin "2") (pinfunction "DOUT_2") (pintype "output"))
    )
    (net (code "67") (name "unconnected-(JP40-Pad1)") (class "Default")
      (node (ref "JP40") (pin "1") (pinfunction "1_1") (pintype "passive"))
    )
    (net (code "68") (name "unconnected-(JP44-Pad1)") (class "Default")
      (node (ref "JP44") (pin "1") (pinfunction "1_1") (pintype "passive"))
    )
    (net (code "69") (name "unconnected-(JP50-Pad1)") (class "Default")
      (node (ref "JP50") (pin "1") (pinfunction "1_1") (pintype "passive"))
    )
    (net (code "70") (name "unconnected-(JP51-Pad1)") (class "Default")
      (node (ref "JP51") (pin "1") (pinfunction "1_1") (pintype "passive"))
    )
    (net (code "71") (name "unconnected-(JP52-Pad1)") (class "Default")
      (node (ref "JP52") (pin "1") (pinfunction "1_1") (pintype "passive"))
    )
    (net (code "72") (name "unconnected-(JP53-Pad1)") (class "Default")
      (node (ref "JP53") (pin "1") (pinfunction "1_1") (pintype "passive"))
    )
    (net (code "73") (name "unconnected-(JP54-Pad1)") (class "Default")
      (node (ref "JP54") (pin "1") (pinfunction "1_1") (pintype "passive"))
    )
    (net (code "74") (name "unconnected-(JP55-Pad1)") (class "Default")
      (node (ref "JP55") (pin "1") (pinfunction "1_1") (pintype "passive"))
    )
    (net (code "75") (name "unconnected-(JP56-Pad1)") (class "Default")
      (node (ref "JP56") (pin "1") (pinfunction "1_1") (pintype "passive"))
    )
    (net (code "76") (name "unconnected-(JP57-Pad1)") (class "Default")
      (node (ref "JP57") (pin "1") (pinfunction "1_1") (pintype "passive"))
    )
    (net (code "77") (name "unconnected-(JP58-Pad1)") (class "Default")
      (node (ref "JP58") (pin "1") (pinfunction "1_1") (pintype "passive"))
    )
    (net (code "78") (name "unconnected-(JP59-Pad1)") (class "Default")
      (node (ref "JP59") (pin "1") (pinfunction "1_1") (pintype "passive"))
    )
    (net (code "79") (name "unconnected-(JP60-Pad1)") (class "Default")
      (node (ref "JP60") (pin "1") (pinfunction "1_1") (pintype "passive"))
    )
    (net (code "80") (name "unconnected-(JP61-Pad1)") (class "Default")
      (node (ref "JP61") (pin "1") (pinfunction "1_1") (pintype "passive"))
    )
    (net (code "81") (name "unconnected-(JP62-Pad1)") (class "Default")
      (node (ref "JP62") (pin "1") (pinfunction "1_1") (pintype "passive"))
    )
    (net (code "82") (name "unconnected-(JP63-Pad1)") (class "Default")
      (node (ref "JP63") (pin "1") (pinfunction "1_1") (pintype "passive"))
    )
    (net (code "83") (name "unconnected-(JP64-Pad1)") (class "Default")
      (node (ref "JP64") (pin "1") (pinfunction "1_1") (pintype "passive"))
    )
    (net (code "84") (name "unconnected-(JP65-Pad1)") (class "Default")
      (node (ref "JP65") (pin "1") (pinfunction "1_1") (pintype "passive"))
    )
    (net (code "85") (name "unconnected-(JP66-Pad1)") (class "Default")
      (node (ref "JP66") (pin "1") (pinfunction "1_1") (pintype "passive"))
    )
    (net (code "86") (name "unconnected-(JP67-Pad1)") (class "Default")
      (node (ref "JP67") (pin "1") (pinfunction "1_1") (pintype "passive"))
    )
    (net (code "87") (name "unconnected-(JP68-Pad1)") (class "Default")
      (node (ref "JP68") (pin "1") (pinfunction "1_1") (pintype "passive"))
    )
    (net (code "88") (name "unconnected-(JP69-Pad1)") (class "Default")
      (node (ref "JP69") (pin "1") (pinfunction "1_1") (pintype "passive"))
    )
    (net (code "89") (name "unconnected-(JP70-Pad1)") (class "Default")
      (node (ref "JP70") (pin "1") (pinfunction "1_1") (pintype "passive"))
    )
    (net (code "90") (name "unconnected-(JP71-Pad1)") (class "Default")
      (node (ref "JP71") (pin "1") (pinfunction "1_1") (pintype "passive"))
    )
    (net (code "91") (name "unconnected-(JP72-Pad1)") (class "Default")
      (node (ref "JP72") (pin "1") (pinfunction "1_1") (pintype "passive"))
    )
    (net (code "92") (name "unconnected-(JP73-Pad1)") (class "Default")
      (node (ref "JP73") (pin "1") (pinfunction "1_1") (pintype "passive"))
    )
    (net (code "93") (name "unconnected-(JP74-Pad1)") (class "Default")
      (node (ref "JP74") (pin "1") (pinfunction "1_1") (pintype "passive"))
    )
    (net (code "94") (name "unconnected-(JP75-Pad1)") (class "Default")
      (node (ref "JP75") (pin "1") (pinfunction "1_1") (pintype "passive"))
    )
  )
)
